# I2C_Air_Pressure_Sensor.net
KiCad netlist of a schematic drawn in Altium Designer
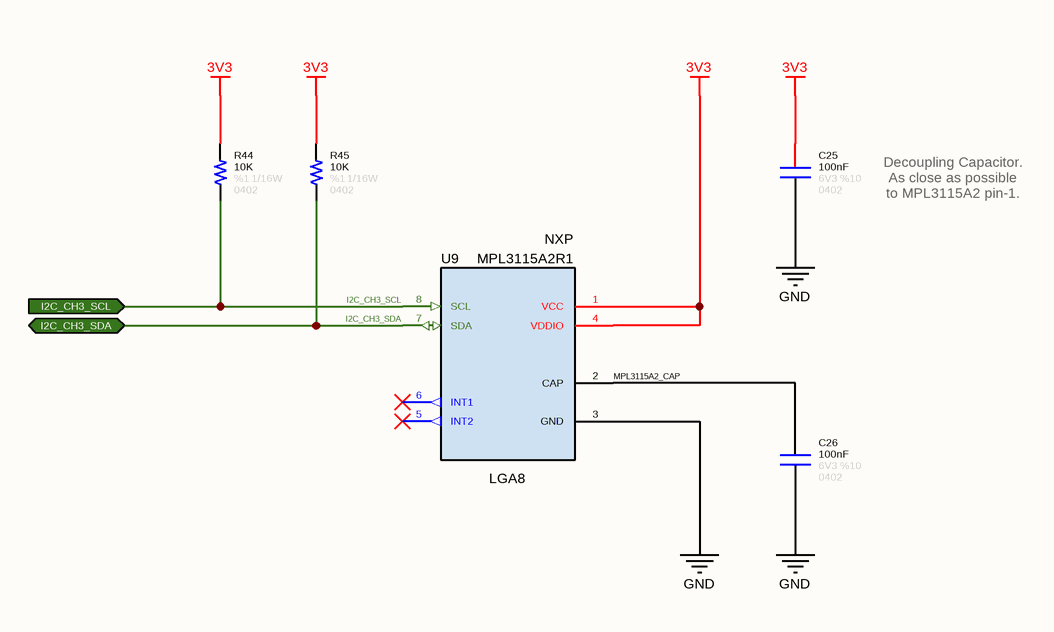
[diagram p0: I2C Air Pressure Sensor.SchDoc]

(export (version "E")
  (design (tool "Eeschema 10.0.6"))
  (components
    (comp (ref "C25")
      (value "100nF")
      (footprint "CAPACITOR_0402")
      (description "Capacitor - 100nF [0402-6V3] (Ceramic)")
      (fields
        (field (name "MANUFACTURER PART NUMBER") "04026D104KAT4A")
        (field (name "TOLERANCE") "%10")
        (field (name "VOLTAGE") "6V3")
        (field (name "CASE") "0402")
        (field (name "Comment") "Capacitor - 100nF [0402] (Ceramic)")
      )
      (libsource (lib "Akkoyun") (part "Capacitor - 100nF [0402-6V3]"))
    )
    (comp (ref "C26")
      (value "100nF")
      (footprint "CAPACITOR_0402")
      (description "Capacitor - 100nF [0402-6V3] (Ceramic)")
      (fields
        (field (name "MANUFACTURER PART NUMBER") "04026D104KAT4A")
        (field (name "TOLERANCE") "%10")
        (field (name "VOLTAGE") "6V3")
        (field (name "CASE") "0402")
        (field (name "Comment") "Capacitor - 100nF [0402] (Ceramic)")
      )
      (libsource (lib "Akkoyun") (part "Capacitor - 100nF [0402-6V3]"))
    )
    (comp (ref "R44")
      (value "10K")
      (footprint "RESISTOR_0402")
      (description "Thick Film Resistors - SMD 1/16 W 10 KOhm 1%")
      (fields
        (field (name "MANUFACTURER PART NUMBER") "CRCW040210K0FKED")
        (field (name "TOLERANCE") "%1")
        (field (name "CASE") "0402")
        (field (name "POWER") "1/16W")
        (field (name "Comment") "10K - 0402 - %1 - 1/16W")
      )
      (libsource (lib "Akkoyun") (part "Resistor - 10K [0402]"))
    )
    (comp (ref "R45")
      (value "10K")
      (footprint "RESISTOR_0402")
      (description "Thick Film Resistors - SMD 1/16 W 10 KOhm 1%")
      (fields
        (field (name "MANUFACTURER PART NUMBER") "CRCW040210K0FKED")
        (field (name "TOLERANCE") "%1")
        (field (name "CASE") "0402")
        (field (name "POWER") "1/16W")
        (field (name "Comment") "10K - 0402 - %1 - 1/16W")
      )
      (libsource (lib "Akkoyun") (part "Resistor - 10K [0402]"))
    )
    (comp (ref "U9")
      (value "MPL3115A2R1")
      (footprint "MPL3115A2")
      (description "Board Mount Pressure Sensors")
      (fields
        (field (name "MANUFACTURER NAME") "NXP")
        (field (name "MANUFACTURER PART NUMBER") "MPL3115A2R1")
        (field (name "CASE") "LGA8")
      )
      (libsource (lib "Akkoyun") (part "IC - MPL3115A2R1"))
    )
  )
  (nets
    (net (code "1") (name "/I2C_CH3_SCL") (class "Default")
      (node (ref "R44") (pin "1") (pinfunction "1_1") (pintype "passive"))
      (node (ref "U9") (pin "8") (pinfunction "SCL_8") (pintype "input"))
    )
    (net (code "2") (name "/I2C_CH3_SDA") (class "Default")
      (node (ref "R45") (pin "1") (pinfunction "1_1") (pintype "passive"))
      (node (ref "U9") (pin "7") (pinfunction "SDA_7") (pintype "bidirectional"))
    )
    (net (code "3") (name "/MPL3115A2_CAP") (class "Default")
      (node (ref "C26") (pin "2") (pinfunction "2_2") (pintype "passive"))
      (node (ref "U9") (pin "2") (pinfunction "CAP_2") (pintype "passive"))
    )
    (net (code "4") (name "3V3") (class "Default")
      (node (ref "C25") (pin "2") (pinfunction "2_2") (pintype "passive"))
      (node (ref "R44") (pin "2") (pinfunction "2_2") (pintype "passive"))
      (node (ref "R45") (pin "2") (pinfunction "2_2") (pintype "passive"))
      (node (ref "U9") (pin "1") (pinfunction "VCC_1") (pintype "power_in"))
      (node (ref "U9") (pin "4") (pinfunction "VDDIO_4") (pintype "power_in"))
    )
    (net (code "5") (name "GND") (class "Default")
      (node (ref "C25") (pin "1") (pinfunction "1_1") (pintype "passive"))
      (node (ref "C26") (pin "1") (pinfunction "1_1") (pintype "passive"))
      (node (ref "U9") (pin "3") (pinfunction "GND_3") (pintype "power_in"))
    )
    (net (code "6") (name "unconnected-(U9-INT1-Pad6)") (class "Default")
      (node (ref "U9") (pin "6") (pinfunction "INT1_6") (pintype "output+no_connect"))
    )
    (net (code "7") (name "unconnected-(U9-INT2-Pad5)") (class "Default")
      (node (ref "U9") (pin "5") (pinfunction "INT2_5") (pintype "output+no_connect"))
    )
  )
)
